# sparkfun-samd21-mini-breakout.net
KiCad netlist of a schematic drawn in EAGLE
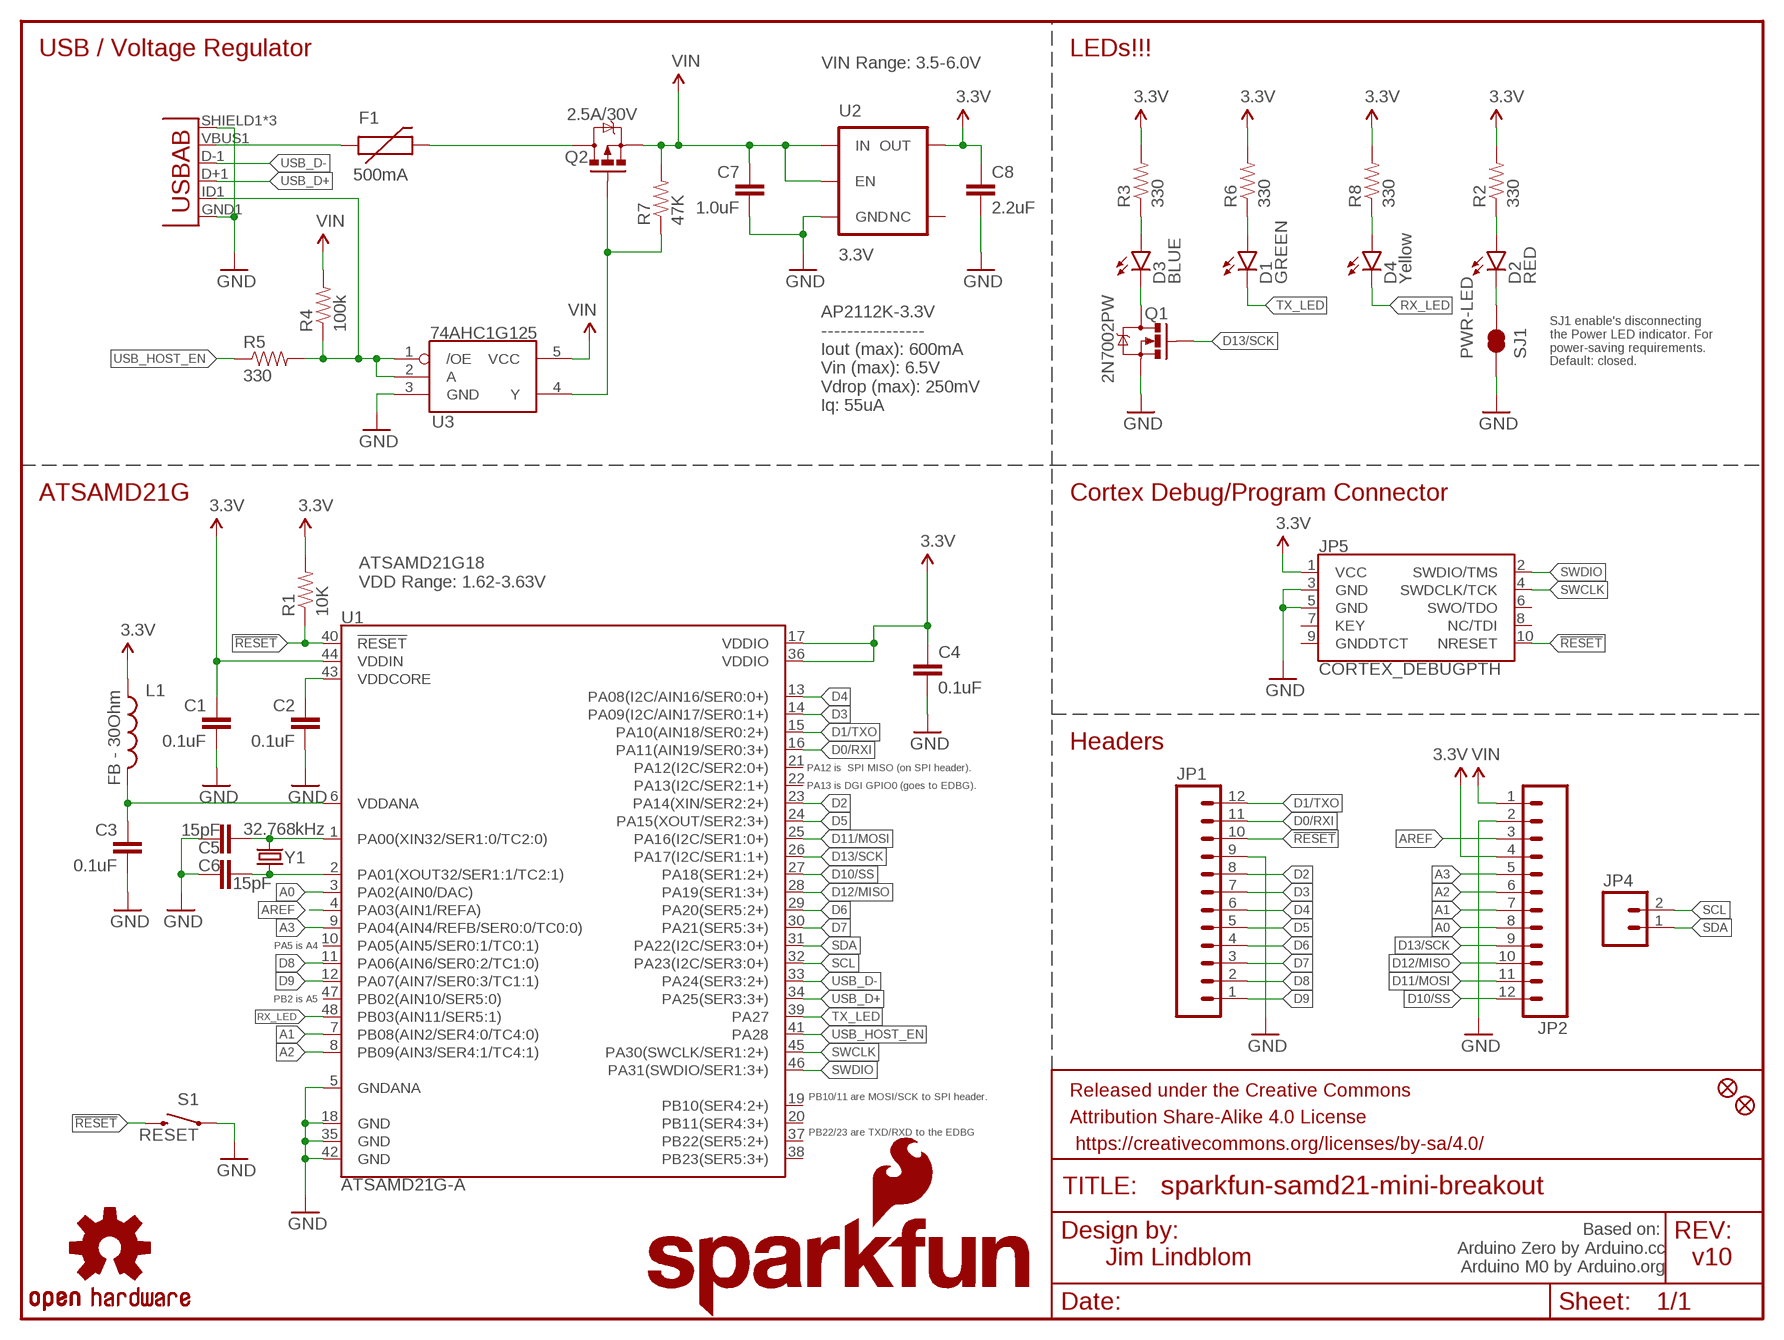
[diagram p0: schematic, sheet 1]

(export (version "E")
  (design (tool "Eeschema 10.0.6"))
  (components
    (comp (ref "C1")
      (value "0.1uF")
      (footprint "eagle-import:0402-CAP")
      (libsource (lib "eagle-import") (part "0.1UF-16V(+-10%)(0402)"))
    )
    (comp (ref "C2")
      (value "0.1uF")
      (footprint "eagle-import:0402-CAP")
      (libsource (lib "eagle-import") (part "0.1UF-16V(+-10%)(0402)"))
    )
    (comp (ref "C3")
      (value "0.1uF")
      (footprint "eagle-import:0402-CAP")
      (libsource (lib "eagle-import") (part "0.1UF-16V(+-10%)(0402)"))
    )
    (comp (ref "C4")
      (value "0.1uF")
      (footprint "eagle-import:0402-CAP")
      (libsource (lib "eagle-import") (part "0.1UF-16V(+-10%)(0402)"))
    )
    (comp (ref "C5")
      (value "15pF")
      (footprint "eagle-import:0402-CAP")
      (libsource (lib "eagle-import") (part "15PF-50V(+-5%)(0402)"))
    )
    (comp (ref "C6")
      (value "15pF")
      (footprint "eagle-import:0402-CAP")
      (libsource (lib "eagle-import") (part "15PF-50V(+-5%)(0402)"))
    )
    (comp (ref "C7")
      (value "1.0uF")
      (footprint "eagle-import:0805-CAP")
      (libsource (lib "eagle-import") (part "1.0UF-25V-+80/-20(0805){dblquote}"))
    )
    (comp (ref "C8")
      (value "2.2uF")
      (footprint "eagle-import:0603-CAP")
      (libsource (lib "eagle-import") (part "2.2UF-10V-20%(0603)"))
    )
    (comp (ref "D1")
      (value "GREEN")
      (footprint "eagle-import:LED-0603")
      (libsource (lib "eagle-import") (part "LED-GREEN0603"))
    )
    (comp (ref "D2")
      (value "RED")
      (footprint "eagle-import:LED-0603")
      (libsource (lib "eagle-import") (part "LED-RED0603"))
    )
    (comp (ref "D3")
      (value "BLUE")
      (footprint "eagle-import:LED-0603")
      (libsource (lib "eagle-import") (part "LED-BLUE0603"))
    )
    (comp (ref "D4")
      (value "Yellow")
      (footprint "eagle-import:LED-0603")
      (libsource (lib "eagle-import") (part "LED-YELLOW0603"))
    )
    (comp (ref "F1")
      (value "500mA")
      (footprint "eagle-import:PTC-1206")
      (libsource (lib "eagle-import") (part "PTCSMD"))
    )
    (comp (ref "FID1")
      (value "FIDUCIAL1X2")
      (footprint "eagle-import:FIDUCIAL-1X2")
      (libsource (lib "eagle-import") (part "FIDUCIAL1X2"))
    )
    (comp (ref "FID2")
      (value "FIDUCIAL1X2")
      (footprint "eagle-import:FIDUCIAL-1X2")
      (libsource (lib "eagle-import") (part "FIDUCIAL1X2"))
    )
    (comp (ref "FRAME1")
      (value "FRAME-LETTER")
      (footprint "eagle-import:CREATIVE_COMMONS")
      (libsource (lib "eagle-import") (part "FRAME-LETTER"))
    )
    (comp (ref "JP1")
      (value "M12NO_SILK")
      (footprint "eagle-import:1X12_NO_SILK")
      (libsource (lib "eagle-import") (part "M12NO_SILK"))
    )
    (comp (ref "JP2")
      (value "M12NO_SILK")
      (footprint "eagle-import:1X12_NO_SILK")
      (libsource (lib "eagle-import") (part "M12NO_SILK"))
    )
    (comp (ref "JP3")
      (value "USB-ABCONN-11794")
      (footprint "eagle-import:USB-AB-MICRO-SMD_V03")
      (libsource (lib "eagle-import") (part "USB-ABCONN-11794"))
    )
    (comp (ref "JP4")
      (value "M021X02_NO_SILK")
      (footprint "eagle-import:1X02_NO_SILK")
      (libsource (lib "eagle-import") (part "M021X02_NO_SILK"))
    )
    (comp (ref "JP5")
      (value "CORTEX_DEBUGPTH")
      (footprint "eagle-import:2X5-PTH-1.27MM")
      (libsource (lib "eagle-import") (part "CORTEX_DEBUGPTH"))
    )
    (comp (ref "L1")
      (value "FB - 30Ohm")
      (footprint "eagle-import:0603")
      (libsource (lib "eagle-import") (part "INDUCTOR0603"))
    )
    (comp (ref "LOGO1")
      (value "SFE_LOGO_FLAME.1_INCH")
      (footprint "eagle-import:SFE_LOGO_FLAME_.1")
      (libsource (lib "eagle-import") (part "SFE_LOGO_FLAME.1_INCH"))
    )
    (comp (ref "LOGO2")
      (value "OSHW-LOGOS")
      (footprint "eagle-import:OSHW-LOGO-S")
      (libsource (lib "eagle-import") (part "OSHW-LOGOS"))
    )
    (comp (ref "LOGO3")
      (value "SFE_LOGO_NAME_FLAME.1_INCH")
      (footprint "eagle-import:SFE_LOGO_NAME_FLAME_.1")
      (libsource (lib "eagle-import") (part "SFE_LOGO_NAME_FLAME.1_INCH"))
    )
    (comp (ref "Q1")
      (value "2N7002PW")
      (footprint "eagle-import:SOT323")
      (libsource (lib "eagle-import") (part "MOSFET-NCHANNEL2N7002PW"))
    )
    (comp (ref "Q2")
      (value "2.5A/30V")
      (footprint "eagle-import:SOT23-3")
      (libsource (lib "eagle-import") (part "MOSFET-PCHANNELDMG2307L"))
    )
    (comp (ref "R1")
      (value "10K")
      (footprint "eagle-import:0603-RES")
      (libsource (lib "eagle-import") (part "10KOHM-1/10W-1%(0603)0603"))
    )
    (comp (ref "R2")
      (value "330")
      (footprint "eagle-import:0603-RES")
      (libsource (lib "eagle-import") (part "330OHM1/10W1%(0603)"))
    )
    (comp (ref "R3")
      (value "330")
      (footprint "eagle-import:0603-RES")
      (libsource (lib "eagle-import") (part "330OHM1/10W1%(0603)"))
    )
    (comp (ref "R4")
      (value "100k")
      (footprint "eagle-import:0603-RES")
      (libsource (lib "eagle-import") (part "100KOHM-1/10W-1%(0603)"))
    )
    (comp (ref "R5")
      (value "330")
      (footprint "eagle-import:0603-RES")
      (libsource (lib "eagle-import") (part "330OHM1/10W1%(0603)"))
    )
    (comp (ref "R6")
      (value "330")
      (footprint "eagle-import:0603-RES")
      (libsource (lib "eagle-import") (part "330OHM1/10W1%(0603)"))
    )
    (comp (ref "R7")
      (value "47K")
      (footprint "eagle-import:0603-RES")
      (libsource (lib "eagle-import") (part "47KOHM1/10W1%(0603)"))
    )
    (comp (ref "R8")
      (value "330")
      (footprint "eagle-import:0603-RES")
      (libsource (lib "eagle-import") (part "330OHM1/10W1%(0603)"))
    )
    (comp (ref "S1")
      (value "RESET")
      (footprint "eagle-import:TACTILE_SWITCH_SMD_4.6X2.8MM")
      (libsource (lib "eagle-import") (part "SWITCH-MOMENTARY-2SMD-4.6X2.8MM"))
    )
    (comp (ref "SJ1")
      (value "PWR-LED")
      (footprint "eagle-import:PAD-JUMPER-2-NC_BY_TRACE_NO_SILK")
      (libsource (lib "eagle-import") (part "JUMPER-PAD-2-NC_BY_TRACENO_SILK"))
    )
    (comp (ref "U1")
      (value "ATSAMD21G-A")
      (footprint "eagle-import:TQFP-48")
      (libsource (lib "eagle-import") (part "ATSAMD21G-A"))
    )
    (comp (ref "U2")
      (value "3.3V")
      (footprint "eagle-import:SOT23-5")
      (libsource (lib "eagle-import") (part "V_REG_AP2112K-3.3V"))
    )
    (comp (ref "U3")
      (value "74AHC1G125")
      (footprint "eagle-import:SOT23-5")
      (libsource (lib "eagle-import") (part "74AHC1G125"))
    )
    (comp (ref "Y1")
      (value "32.768kHz")
      (footprint "eagle-import:CRYSTAL-SMD-3.2X1.5MM")
      (libsource (lib "eagle-import") (part "CRYSTAL3.2X1.5MM"))
    )
  )
  (nets
    (net (code "1") (name "/~{RESET}") (class "Default")
      (node (ref "JP1") (pin "10") (pinfunction "10_10") (pintype "passive"))
      (node (ref "JP5") (pin "10") (pinfunction "NRESET_10") (pintype "bidirectional"))
      (node (ref "R1") (pin "1") (pinfunction "1_1") (pintype "passive"))
      (node (ref "S1") (pin "3") (pinfunction "2_3") (pintype "passive"))
      (node (ref "S1") (pin "4") (pinfunction "2_4") (pintype "passive"))
      (node (ref "U1") (pin "40") (pinfunction "~{RESET}_40") (pintype "bidirectional"))
    )
    (net (code "2") (name "3.3V") (class "Default")
      (node (ref "C1") (pin "1") (pinfunction "1_1") (pintype "passive"))
      (node (ref "C4") (pin "1") (pinfunction "1_1") (pintype "passive"))
      (node (ref "C8") (pin "1") (pinfunction "1_1") (pintype "passive"))
      (node (ref "JP2") (pin "4") (pinfunction "4_4") (pintype "passive"))
      (node (ref "JP5") (pin "1") (pinfunction "VCC_1") (pintype "bidirectional"))
      (node (ref "L1") (pin "1") (pinfunction "1_1") (pintype "passive"))
      (node (ref "R1") (pin "2") (pinfunction "2_2") (pintype "passive"))
      (node (ref "R2") (pin "2") (pinfunction "2_2") (pintype "passive"))
      (node (ref "R3") (pin "2") (pinfunction "2_2") (pintype "passive"))
      (node (ref "R6") (pin "2") (pinfunction "2_2") (pintype "passive"))
      (node (ref "R8") (pin "2") (pinfunction "2_2") (pintype "passive"))
      (node (ref "U1") (pin "17") (pinfunction "VDDIO_17") (pintype "bidirectional"))
      (node (ref "U1") (pin "36") (pinfunction "VDDIO_36") (pintype "bidirectional"))
      (node (ref "U1") (pin "44") (pinfunction "VDDIN_44") (pintype "bidirectional"))
      (node (ref "U2") (pin "5") (pinfunction "OUT_5") (pintype "passive"))
    )
    (net (code "3") (name "A0") (class "Default")
      (node (ref "JP2") (pin "8") (pinfunction "8_8") (pintype "passive"))
      (node (ref "U1") (pin "3") (pinfunction "PA02(AIN0/DAC)_3") (pintype "bidirectional"))
    )
    (net (code "4") (name "A1") (class "Default")
      (node (ref "JP2") (pin "7") (pinfunction "7_7") (pintype "passive"))
      (node (ref "U1") (pin "7") (pinfunction "PB08(AIN2/SER4:0/TC4:0)_7") (pintype "bidirectional"))
    )
    (net (code "5") (name "A2") (class "Default")
      (node (ref "JP2") (pin "6") (pinfunction "6_6") (pintype "passive"))
      (node (ref "U1") (pin "8") (pinfunction "PB09(AIN3/SER4:1/TC4:1)_8") (pintype "bidirectional"))
    )
    (net (code "6") (name "A3") (class "Default")
      (node (ref "JP2") (pin "5") (pinfunction "5_5") (pintype "passive"))
      (node (ref "U1") (pin "9") (pinfunction "PA04(AIN4/REFB/SER0:0/TC0:0)_9") (pintype "bidirectional"))
    )
    (net (code "7") (name "AREF") (class "Default")
      (node (ref "JP2") (pin "3") (pinfunction "3_3") (pintype "passive"))
      (node (ref "U1") (pin "4") (pinfunction "PA03(AIN1/REFA)_4") (pintype "bidirectional"))
    )
    (net (code "8") (name "D0{slash}RXI") (class "Default")
      (node (ref "JP1") (pin "11") (pinfunction "11_11") (pintype "passive"))
      (node (ref "U1") (pin "16") (pinfunction "PA11(AIN19/SER0:3+)_16") (pintype "bidirectional"))
    )
    (net (code "9") (name "D1{slash}TXO") (class "Default")
      (node (ref "JP1") (pin "12") (pinfunction "12_12") (pintype "passive"))
      (node (ref "U1") (pin "15") (pinfunction "PA10(AIN18/SER0:2+)_15") (pintype "bidirectional"))
    )
    (net (code "10") (name "D2") (class "Default")
      (node (ref "JP1") (pin "8") (pinfunction "8_8") (pintype "passive"))
      (node (ref "U1") (pin "23") (pinfunction "PA14(XIN/SER2:2+)_23") (pintype "bidirectional"))
    )
    (net (code "11") (name "D3") (class "Default")
      (node (ref "JP1") (pin "7") (pinfunction "7_7") (pintype "passive"))
      (node (ref "U1") (pin "14") (pinfunction "PA09(I2C/AIN17/SER0:1+)_14") (pintype "bidirectional"))
    )
    (net (code "12") (name "D4") (class "Default")
      (node (ref "JP1") (pin "6") (pinfunction "6_6") (pintype "passive"))
      (node (ref "U1") (pin "13") (pinfunction "PA08(I2C/AIN16/SER0:0+)_13") (pintype "bidirectional"))
    )
    (net (code "13") (name "D5") (class "Default")
      (node (ref "JP1") (pin "5") (pinfunction "5_5") (pintype "passive"))
      (node (ref "U1") (pin "24") (pinfunction "PA15(XOUT/SER2:3+)_24") (pintype "bidirectional"))
    )
    (net (code "14") (name "D6") (class "Default")
      (node (ref "JP1") (pin "4") (pinfunction "4_4") (pintype "passive"))
      (node (ref "U1") (pin "29") (pinfunction "PA20(SER5:2+)_29") (pintype "bidirectional"))
    )
    (net (code "15") (name "D7") (class "Default")
      (node (ref "JP1") (pin "3") (pinfunction "3_3") (pintype "passive"))
      (node (ref "U1") (pin "30") (pinfunction "PA21(SER5:3+)_30") (pintype "bidirectional"))
    )
    (net (code "16") (name "D8") (class "Default")
      (node (ref "JP1") (pin "2") (pinfunction "2_2") (pintype "passive"))
      (node (ref "U1") (pin "11") (pinfunction "PA06(AIN6/SER0:2/TC1:0)_11") (pintype "bidirectional"))
    )
    (net (code "17") (name "D9") (class "Default")
      (node (ref "JP1") (pin "1") (pinfunction "1_1") (pintype "passive"))
      (node (ref "U1") (pin "12") (pinfunction "PA07(AIN7/SER0:3/TC1:1)_12") (pintype "bidirectional"))
    )
    (net (code "18") (name "D10{slash}SS") (class "Default")
      (node (ref "JP2") (pin "12") (pinfunction "12_12") (pintype "passive"))
      (node (ref "U1") (pin "27") (pinfunction "PA18(SER1:2+)_27") (pintype "bidirectional"))
    )
    (net (code "19") (name "D11{slash}MOSI") (class "Default")
      (node (ref "JP2") (pin "11") (pinfunction "11_11") (pintype "passive"))
      (node (ref "U1") (pin "25") (pinfunction "PA16(I2C/SER1:0+)_25") (pintype "bidirectional"))
    )
    (net (code "20") (name "D12{slash}MISO") (class "Default")
      (node (ref "JP2") (pin "10") (pinfunction "10_10") (pintype "passive"))
      (node (ref "U1") (pin "28") (pinfunction "PA19(SER1:3+)_28") (pintype "bidirectional"))
    )
    (net (code "21") (name "D13{slash}SCK") (class "Default")
      (node (ref "JP2") (pin "9") (pinfunction "9_9") (pintype "passive"))
      (node (ref "Q1") (pin "1") (pinfunction "G_1") (pintype "passive"))
      (node (ref "U1") (pin "26") (pinfunction "PA17(I2C/SER1:1+)_26") (pintype "bidirectional"))
    )
    (net (code "22") (name "GND") (class "Default")
      (node (ref "C1") (pin "2") (pinfunction "2_2") (pintype "passive"))
      (node (ref "C2") (pin "2") (pinfunction "2_2") (pintype "passive"))
      (node (ref "C3") (pin "2") (pinfunction "2_2") (pintype "passive"))
      (node (ref "C4") (pin "2") (pinfunction "2_2") (pintype "passive"))
      (node (ref "C5") (pin "1") (pinfunction "1_1") (pintype "passive"))
      (node (ref "C6") (pin "2") (pinfunction "2_2") (pintype "passive"))
      (node (ref "C7") (pin "2") (pinfunction "2_2") (pintype "passive"))
      (node (ref "C8") (pin "2") (pinfunction "2_2") (pintype "passive"))
      (node (ref "JP1") (pin "9") (pinfunction "9_9") (pintype "passive"))
      (node (ref "JP2") (pin "2") (pinfunction "2_2") (pintype "passive"))
      (node (ref "JP3") (pin "GND1") (pinfunction "GND_GND1") (pintype "bidirectional"))
      (node (ref "JP3") (pin "SHIELD1") (pinfunction "SHIELD_SHIELD1") (pintype "bidirectional"))
      (node (ref "JP3") (pin "SHIELD2") (pinfunction "SHIELD_SHIELD2") (pintype "bidirectional"))
      (node (ref "JP3") (pin "SHIELD3") (pinfunction "SHIELD_SHIELD3") (pintype "bidirectional"))
      (node (ref "JP5") (pin "3") (pinfunction "GND_3") (pintype "bidirectional"))
      (node (ref "JP5") (pin "5") (pinfunction "GND_5") (pintype "bidirectional"))
      (node (ref "Q1") (pin "2") (pinfunction "S_2") (pintype "passive"))
      (node (ref "S1") (pin "1") (pinfunction "1_1") (pintype "passive"))
      (node (ref "S1") (pin "2") (pinfunction "1_2") (pintype "passive"))
      (node (ref "SJ1") (pin "1") (pinfunction "1_1") (pintype "passive"))
      (node (ref "U1") (pin "18") (pinfunction "GND_18") (pintype "bidirectional"))
      (node (ref "U1") (pin "35") (pinfunction "GND_35") (pintype "bidirectional"))
      (node (ref "U1") (pin "42") (pinfunction "GND_42") (pintype "bidirectional"))
      (node (ref "U1") (pin "5") (pinfunction "GNDANA_5") (pintype "bidirectional"))
      (node (ref "U2") (pin "2") (pinfunction "GND_2") (pintype "input"))
      (node (ref "U3") (pin "3") (pinfunction "GND_3") (pintype "bidirectional"))
    )
    (net (code "23") (name "Net-(D1-PadA)") (class "Default")
      (node (ref "D1") (pin "A") (pinfunction "A_A") (pintype "passive"))
      (node (ref "R6") (pin "1") (pinfunction "1_1") (pintype "passive"))
    )
    (net (code "24") (name "Net-(D2-PadA)") (class "Default")
      (node (ref "D2") (pin "A") (pinfunction "A_A") (pintype "passive"))
      (node (ref "R2") (pin "1") (pinfunction "1_1") (pintype "passive"))
    )
    (net (code "25") (name "Net-(D2-PadC)") (class "Default")
      (node (ref "D2") (pin "C") (pinfunction "C_C") (pintype "passive"))
      (node (ref "SJ1") (pin "2") (pinfunction "2_2") (pintype "passive"))
    )
    (net (code "26") (name "Net-(D3-PadA)") (class "Default")
      (node (ref "D3") (pin "A") (pinfunction "A_A") (pintype "passive"))
      (node (ref "R3") (pin "1") (pinfunction "1_1") (pintype "passive"))
    )
    (net (code "27") (name "Net-(D4-PadA)") (class "Default")
      (node (ref "D4") (pin "A") (pinfunction "A_A") (pintype "passive"))
      (node (ref "R8") (pin "1") (pinfunction "1_1") (pintype "passive"))
    )
    (net (code "28") (name "Net-(JP3-USBID)") (class "Default")
      (node (ref "JP3") (pin "ID1") (pinfunction "USBID_ID1") (pintype "bidirectional"))
      (node (ref "R4") (pin "1") (pinfunction "1_1") (pintype "passive"))
      (node (ref "R5") (pin "2") (pinfunction "2_2") (pintype "passive"))
      (node (ref "U3") (pin "1") (pinfunction "/OE_1") (pintype "bidirectional"))
      (node (ref "U3") (pin "2") (pinfunction "A_2") (pintype "bidirectional"))
    )
    (net (code "29") (name "Net-(JP3-VBUS)") (class "Default")
      (node (ref "F1") (pin "1") (pinfunction "1_1") (pintype "bidirectional"))
      (node (ref "JP3") (pin "VBUS1") (pinfunction "VBUS_VBUS1") (pintype "bidirectional"))
    )
    (net (code "30") (name "Net-(Q1-D)") (class "Default")
      (node (ref "D3") (pin "C") (pinfunction "C_C") (pintype "passive"))
      (node (ref "Q1") (pin "3") (pinfunction "D_3") (pintype "passive"))
    )
    (net (code "31") (name "Net-(Q2-D)") (class "Default")
      (node (ref "F1") (pin "2") (pinfunction "2_2") (pintype "bidirectional"))
      (node (ref "Q2") (pin "3") (pinfunction "D_3") (pintype "passive"))
    )
    (net (code "32") (name "Net-(Q2-G)") (class "Default")
      (node (ref "Q2") (pin "1") (pinfunction "G_1") (pintype "passive"))
      (node (ref "R7") (pin "1") (pinfunction "1_1") (pintype "passive"))
      (node (ref "U3") (pin "4") (pinfunction "Y_4") (pintype "bidirectional"))
    )
    (net (code "33") (name "Net-(U1-PA00(XIN32{slash}SER1:0{slash}TC2:0))") (class "Default")
      (node (ref "C5") (pin "2") (pinfunction "2_2") (pintype "passive"))
      (node (ref "U1") (pin "1") (pinfunction "PA00(XIN32/SER1:0/TC2:0)_1") (pintype "bidirectional"))
      (node (ref "Y1") (pin "P$2") (pinfunction "2_P$2") (pintype "passive"))
    )
    (net (code "34") (name "Net-(U1-PA01(XOUT32{slash}SER1:1{slash}TC2:1))") (class "Default")
      (node (ref "C6") (pin "1") (pinfunction "1_1") (pintype "passive"))
      (node (ref "U1") (pin "2") (pinfunction "PA01(XOUT32/SER1:1/TC2:1)_2") (pintype "bidirectional"))
      (node (ref "Y1") (pin "P$1") (pinfunction "1_P$1") (pintype "passive"))
    )
    (net (code "35") (name "Net-(U1-VDDANA)") (class "Default")
      (node (ref "C3") (pin "1") (pinfunction "1_1") (pintype "passive"))
      (node (ref "L1") (pin "2") (pinfunction "2_2") (pintype "passive"))
      (node (ref "U1") (pin "6") (pinfunction "VDDANA_6") (pintype "bidirectional"))
    )
    (net (code "36") (name "Net-(U1-VDDCORE)") (class "Default")
      (node (ref "C2") (pin "1") (pinfunction "1_1") (pintype "passive"))
      (node (ref "U1") (pin "43") (pinfunction "VDDCORE_43") (pintype "bidirectional"))
    )
    (net (code "37") (name "RX_LED") (class "Default")
      (node (ref "D4") (pin "C") (pinfunction "C_C") (pintype "passive"))
      (node (ref "U1") (pin "48") (pinfunction "PB03(AIN11/SER5:1)_48") (pintype "bidirectional"))
    )
    (net (code "38") (name "SCL") (class "Default")
      (node (ref "JP4") (pin "2") (pinfunction "2_2") (pintype "passive"))
      (node (ref "U1") (pin "32") (pinfunction "PA23(I2C/SER3:0+)_32") (pintype "bidirectional"))
    )
    (net (code "39") (name "SDA") (class "Default")
      (node (ref "JP4") (pin "1") (pinfunction "1_1") (pintype "passive"))
      (node (ref "U1") (pin "31") (pinfunction "PA22(I2C/SER3:0+)_31") (pintype "bidirectional"))
    )
    (net (code "40") (name "SWCLK") (class "Default")
      (node (ref "JP5") (pin "4") (pinfunction "SWDCLK/TCK_4") (pintype "bidirectional"))
      (node (ref "U1") (pin "45") (pinfunction "PA30(SWCLK/SER1:2+)_45") (pintype "bidirectional"))
    )
    (net (code "41") (name "SWDIO") (class "Default")
      (node (ref "JP5") (pin "2") (pinfunction "SWDIO/TMS_2") (pintype "bidirectional"))
      (node (ref "U1") (pin "46") (pinfunction "PA31(SWDIO/SER1:3+)_46") (pintype "bidirectional"))
    )
    (net (code "42") (name "TX_LED") (class "Default")
      (node (ref "D1") (pin "C") (pinfunction "C_C") (pintype "passive"))
      (node (ref "U1") (pin "39") (pinfunction "PA27_39") (pintype "bidirectional"))
    )
    (net (code "43") (name "USB_D+") (class "Default")
      (node (ref "JP3") (pin "D+1") (pinfunction "D+_D+1") (pintype "bidirectional"))
      (node (ref "U1") (pin "34") (pinfunction "PA25(SER3:3+)_34") (pintype "bidirectional"))
    )
    (net (code "44") (name "USB_D-") (class "Default")
      (node (ref "JP3") (pin "D-1") (pinfunction "D-_D-1") (pintype "bidirectional"))
      (node (ref "U1") (pin "33") (pinfunction "PA24(SER3:2+)_33") (pintype "bidirectional"))
    )
    (net (code "45") (name "USB_HOST_EN") (class "Default")
      (node (ref "R5") (pin "1") (pinfunction "1_1") (pintype "passive"))
      (node (ref "U1") (pin "41") (pinfunction "PA28_41") (pintype "bidirectional"))
    )
    (net (code "46") (name "VIN") (class "Default")
      (node (ref "C7") (pin "1") (pinfunction "1_1") (pintype "passive"))
      (node (ref "JP2") (pin "1") (pinfunction "1_1") (pintype "passive"))
      (node (ref "Q2") (pin "2") (pinfunction "S_2") (pintype "passive"))
      (node (ref "R4") (pin "2") (pinfunction "2_2") (pintype "passive"))
      (node (ref "R7") (pin "2") (pinfunction "2_2") (pintype "passive"))
      (node (ref "U2") (pin "1") (pinfunction "IN_1") (pintype "input"))
      (node (ref "U2") (pin "3") (pinfunction "EN_3") (pintype "input"))
      (node (ref "U3") (pin "5") (pinfunction "VCC_5") (pintype "bidirectional"))
    )
    (net (code "47") (name "unconnected-(JP5-GNDDTCT-Pad9)") (class "Default")
      (node (ref "JP5") (pin "9") (pinfunction "GNDDTCT_9") (pintype "bidirectional"))
    )
    (net (code "48") (name "unconnected-(JP5-KEY-Pad7)") (class "Default")
      (node (ref "JP5") (pin "7") (pinfunction "KEY_7") (pintype "bidirectional"))
    )
    (net (code "49") (name "unconnected-(JP5-NC{slash}TDI-Pad8)") (class "Default")
      (node (ref "JP5") (pin "8") (pinfunction "NC/TDI_8") (pintype "bidirectional"))
    )
    (net (code "50") (name "unconnected-(JP5-SWO{slash}TDO-Pad6)") (class "Default")
      (node (ref "JP5") (pin "6") (pinfunction "SWO/TDO_6") (pintype "bidirectional"))
    )
    (net (code "51") (name "unconnected-(U1-PA05(AIN5{slash}SER0:1{slash}TC0:1)-Pad10)") (class "Default")
      (node (ref "U1") (pin "10") (pinfunction "PA05(AIN5/SER0:1/TC0:1)_10") (pintype "bidirectional"))
    )
    (net (code "52") (name "unconnected-(U1-PA12(I2C{slash}SER2:0+)-Pad21)") (class "Default")
      (node (ref "U1") (pin "21") (pinfunction "PA12(I2C/SER2:0+)_21") (pintype "bidirectional"))
    )
    (net (code "53") (name "unconnected-(U1-PA13(I2C{slash}SER2:1+)-Pad22)") (class "Default")
      (node (ref "U1") (pin "22") (pinfunction "PA13(I2C/SER2:1+)_22") (pintype "bidirectional"))
    )
    (net (code "54") (name "unconnected-(U1-PB02(AIN10{slash}SER5:0)-Pad47)") (class "Default")
      (node (ref "U1") (pin "47") (pinfunction "PB02(AIN10/SER5:0)_47") (pintype "bidirectional"))
    )
    (net (code "55") (name "unconnected-(U1-PB10(SER4:2+)-Pad19)") (class "Default")
      (node (ref "U1") (pin "19") (pinfunction "PB10(SER4:2+)_19") (pintype "bidirectional"))
    )
    (net (code "56") (name "unconnected-(U1-PB11(SER4:3+)-Pad20)") (class "Default")
      (node (ref "U1") (pin "20") (pinfunction "PB11(SER4:3+)_20") (pintype "bidirectional"))
    )
    (net (code "57") (name "unconnected-(U1-PB22(SER5:2+)-Pad37)") (class "Default")
      (node (ref "U1") (pin "37") (pinfunction "PB22(SER5:2+)_37") (pintype "bidirectional"))
    )
    (net (code "58") (name "unconnected-(U1-PB23(SER5:3+)-Pad38)") (class "Default")
      (node (ref "U1") (pin "38") (pinfunction "PB23(SER5:3+)_38") (pintype "bidirectional"))
    )
    (net (code "59") (name "unconnected-(U2-NC-Pad4)") (class "Default")
      (node (ref "U2") (pin "4") (pinfunction "NC_4") (pintype "input"))
    )
  )
)
